# xbee_compat.net
KiCad netlist of a schematic drawn in EAGLE
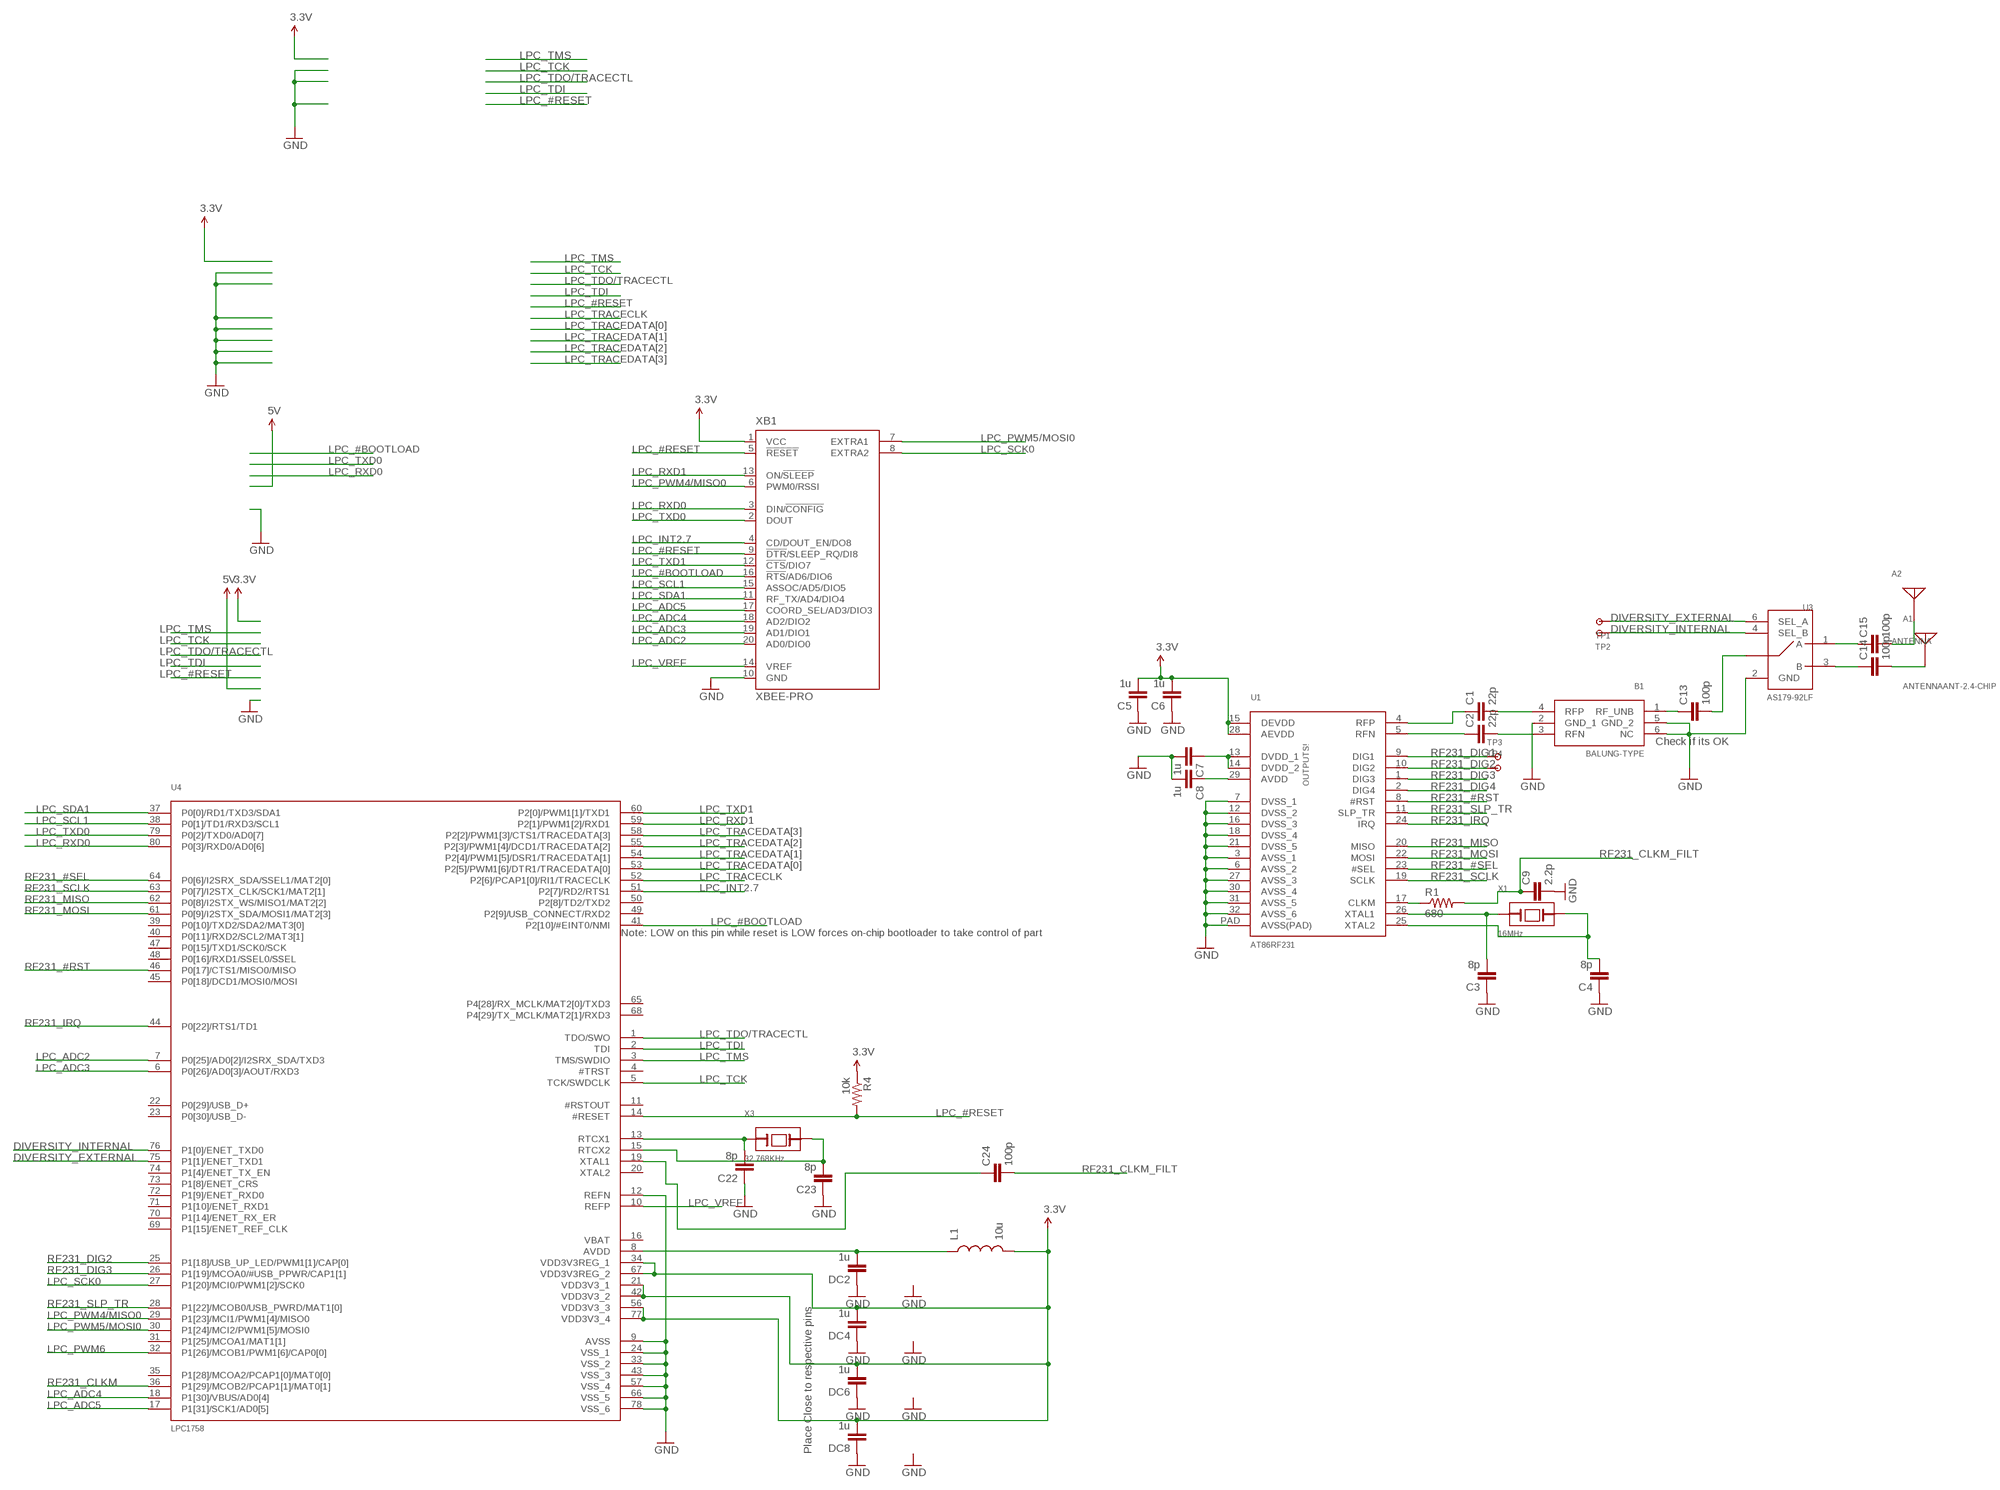
[diagram p0: schematic, sheet 1]

(export (version "E")
  (design (tool "Eeschema 10.0.6"))
  (components
    (comp (ref "A1")
      (value "ANTENNAANT-2.4-CHIP")
      (footprint "eagle-import:ANT-2.4-CHP")
      (libsource (lib "eagle-import") (part "ANTENNAANT-2.4-CHIP"))
    )
    (comp (ref "A2")
      (value "ANTENNA")
      (footprint "eagle-import:CONREVSMA003.031")
      (libsource (lib "eagle-import") (part "ANTENNA"))
    )
    (comp (ref "B1")
      (value "BALUNG-TYPE")
      (footprint "eagle-import:MURATA_LDB_BALUN")
      (libsource (lib "eagle-import") (part "BALUNG-TYPE"))
    )
    (comp (ref "C1")
      (value "22p")
      (footprint "eagle-import:C0402")
      (libsource (lib "eagle-import") (part "CAP0402"))
    )
    (comp (ref "C2")
      (value "22p")
      (footprint "eagle-import:C0402")
      (libsource (lib "eagle-import") (part "CAP0402"))
    )
    (comp (ref "C3")
      (value "8p")
      (footprint "eagle-import:C0402")
      (libsource (lib "eagle-import") (part "CAP0402"))
    )
    (comp (ref "C4")
      (value "8p")
      (footprint "eagle-import:C0402")
      (libsource (lib "eagle-import") (part "CAP0402"))
    )
    (comp (ref "C5")
      (value "1u")
      (footprint "eagle-import:C0402")
      (libsource (lib "eagle-import") (part "CAP0402"))
    )
    (comp (ref "C6")
      (value "1u")
      (footprint "eagle-import:C0402")
      (libsource (lib "eagle-import") (part "CAP0402"))
    )
    (comp (ref "C7")
      (value "1u")
      (footprint "eagle-import:C0402")
      (libsource (lib "eagle-import") (part "CAP0402"))
    )
    (comp (ref "C8")
      (value "1u")
      (footprint "eagle-import:C0402")
      (libsource (lib "eagle-import") (part "CAP0402"))
    )
    (comp (ref "C9")
      (value "2.2p")
      (footprint "eagle-import:C0402")
      (libsource (lib "eagle-import") (part "CAP0402"))
    )
    (comp (ref "C13")
      (value "100p")
      (footprint "eagle-import:C0402")
      (libsource (lib "eagle-import") (part "CAP0402"))
    )
    (comp (ref "C14")
      (value "100p")
      (footprint "eagle-import:C0402")
      (libsource (lib "eagle-import") (part "CAP0402"))
    )
    (comp (ref "C15")
      (value "100p")
      (footprint "eagle-import:C0402")
      (libsource (lib "eagle-import") (part "CAP0402"))
    )
    (comp (ref "C22")
      (value "8p")
      (footprint "eagle-import:C0402")
      (libsource (lib "eagle-import") (part "CAP0402"))
    )
    (comp (ref "C23")
      (value "8p")
      (footprint "eagle-import:C0402")
      (libsource (lib "eagle-import") (part "CAP0402"))
    )
    (comp (ref "C24")
      (value "100p")
      (footprint "eagle-import:C0402")
      (libsource (lib "eagle-import") (part "CAP0402"))
    )
    (comp (ref "DC2")
      (value "1u")
      (footprint "eagle-import:C0402")
      (libsource (lib "eagle-import") (part "CAP0402"))
    )
    (comp (ref "DC4")
      (value "1u")
      (footprint "eagle-import:C0402")
      (libsource (lib "eagle-import") (part "CAP0402"))
    )
    (comp (ref "DC6")
      (value "1u")
      (footprint "eagle-import:C0402")
      (libsource (lib "eagle-import") (part "CAP0402"))
    )
    (comp (ref "DC8")
      (value "1u")
      (footprint "eagle-import:C0402")
      (libsource (lib "eagle-import") (part "CAP0402"))
    )
    (comp (ref "L1")
      (value "10u")
      (footprint "eagle-import:0603")
      (libsource (lib "eagle-import") (part "INDUCTOR0603"))
    )
    (comp (ref "R1")
      (value "680")
      (footprint "eagle-import:C0402")
      (libsource (lib "eagle-import") (part "RESISTOR0402"))
    )
    (comp (ref "R4")
      (value "10k")
      (footprint "eagle-import:C0402")
      (libsource (lib "eagle-import") (part "RESISTOR0402"))
    )
    (comp (ref "TP1")
      (value "TESTPOINTSMALLEST")
      (footprint "eagle-import:TESTPOINT")
      (libsource (lib "eagle-import") (part "TESTPOINTSMALLEST"))
    )
    (comp (ref "TP2")
      (value "TESTPOINTSMALLEST")
      (footprint "eagle-import:TESTPOINT")
      (libsource (lib "eagle-import") (part "TESTPOINTSMALLEST"))
    )
    (comp (ref "TP3")
      (value "TESTPOINTSMALLEST")
      (footprint "eagle-import:TESTPOINT")
      (libsource (lib "eagle-import") (part "TESTPOINTSMALLEST"))
    )
    (comp (ref "TP4")
      (value "TESTPOINTSMALLEST")
      (footprint "eagle-import:TESTPOINT")
      (libsource (lib "eagle-import") (part "TESTPOINTSMALLEST"))
    )
    (comp (ref "U1")
      (value "AT86RF231")
      (footprint "eagle-import:ATRF231_32QN2")
      (libsource (lib "eagle-import") (part "AT86RF231"))
    )
    (comp (ref "U3")
      (value "AS179-92LF")
      (footprint "eagle-import:SC-70")
      (libsource (lib "eagle-import") (part "AS179-92LF"))
    )
    (comp (ref "U4")
      (value "LPC1758")
      (footprint "eagle-import:LPC1758_LQFP80")
      (libsource (lib "eagle-import") (part "LPC1758"))
    )
    (comp (ref "X1")
      (value "16MHz")
      (footprint "eagle-import:CX3225SA")
      (libsource (lib "eagle-import") (part "XTALCX3225SA"))
    )
    (comp (ref "X3")
      (value "32.768KHz")
      (footprint "eagle-import:ABS07")
      (libsource (lib "eagle-import") (part "XTALABS07"))
    )
    (comp (ref "XB1")
      (value "XBEE-PRO")
      (footprint "eagle-import:XBEE-PRO")
      (libsource (lib "eagle-import") (part "XBEE-PRO"))
    )
  )
  (nets
    (net (code "1") (name "/DIVERSITY_EXTERNAL") (class "Default")
      (node (ref "TP1") (pin "P$1") (pinfunction "P$1_P$1") (pintype "bidirectional"))
      (node (ref "U3") (pin "6") (pinfunction "SEL_A_6") (pintype "bidirectional"))
      (node (ref "U4") (pin "75") (pinfunction "P1[1]/ENET_TXD1_75") (pintype "bidirectional"))
    )
    (net (code "2") (name "/DIVERSITY_INTERNAL") (class "Default")
      (node (ref "TP2") (pin "P$1") (pinfunction "P$1_P$1") (pintype "bidirectional"))
      (node (ref "U3") (pin "4") (pinfunction "SEL_B_4") (pintype "bidirectional"))
      (node (ref "U4") (pin "76") (pinfunction "P1[0]/ENET_TXD0_76") (pintype "bidirectional"))
    )
    (net (code "3") (name "/LPC_#BOOTLOAD") (class "Default")
      (node (ref "U4") (pin "41") (pinfunction "P2[10]/#EINT0/NMI_41") (pintype "bidirectional"))
      (node (ref "XB1") (pin "16") (pinfunction "~{RTS}/AD6/DIO6_16") (pintype "bidirectional"))
    )
    (net (code "4") (name "/LPC_#RESET") (class "Default")
      (node (ref "R4") (pin "2") (pinfunction "2_2") (pintype "passive"))
      (node (ref "U4") (pin "14") (pinfunction "#RESET_14") (pintype "bidirectional"))
      (node (ref "XB1") (pin "5") (pinfunction "~{RESET}_5") (pintype "input"))
      (node (ref "XB1") (pin "9") (pinfunction "~{DTR}/SLEEP_RQ/DI8_9") (pintype "bidirectional"))
    )
    (net (code "5") (name "/LPC_ADC2") (class "Default")
      (node (ref "U4") (pin "7") (pinfunction "P0[25]/AD0[2]/I2SRX_SDA/TXD3_7") (pintype "bidirectional"))
      (node (ref "XB1") (pin "20") (pinfunction "AD0/DIO0_20") (pintype "bidirectional"))
    )
    (net (code "6") (name "/LPC_ADC3") (class "Default")
      (node (ref "U4") (pin "6") (pinfunction "P0[26]/AD0[3]/AOUT/RXD3_6") (pintype "bidirectional"))
      (node (ref "XB1") (pin "19") (pinfunction "AD1/DIO1_19") (pintype "bidirectional"))
    )
    (net (code "7") (name "/LPC_ADC4") (class "Default")
      (node (ref "U4") (pin "18") (pinfunction "P1[30]/VBUS/AD0[4]_18") (pintype "bidirectional"))
      (node (ref "XB1") (pin "18") (pinfunction "AD2/DIO2_18") (pintype "bidirectional"))
    )
    (net (code "8") (name "/LPC_ADC5") (class "Default")
      (node (ref "U4") (pin "17") (pinfunction "P1[31]/SCK1/AD0[5]_17") (pintype "bidirectional"))
      (node (ref "XB1") (pin "17") (pinfunction "COORD_SEL/AD3/DIO3_17") (pintype "bidirectional"))
    )
    (net (code "9") (name "/LPC_INT2.7") (class "Default")
      (node (ref "U4") (pin "51") (pinfunction "P2[7]/RD2/RTS1_51") (pintype "bidirectional"))
      (node (ref "XB1") (pin "4") (pinfunction "CD/DOUT_EN/DO8_4") (pintype "output"))
    )
    (net (code "10") (name "/LPC_PWM4{slash}MISO0") (class "Default")
      (node (ref "U4") (pin "29") (pinfunction "P1[23]/MCI1/PWM1[4]/MISO0_29") (pintype "bidirectional"))
      (node (ref "XB1") (pin "6") (pinfunction "PWM0/RSSI_6") (pintype "output"))
    )
    (net (code "11") (name "/LPC_PWM5{slash}MOSI0") (class "Default")
      (node (ref "U4") (pin "30") (pinfunction "P1[24]/MCI2/PWM1[5]/MOSI0_30") (pintype "bidirectional"))
      (node (ref "XB1") (pin "7") (pinfunction "EXTRA1_7") (pintype "bidirectional"))
    )
    (net (code "12") (name "/LPC_PWM6") (class "Default")
      (node (ref "U4") (pin "32") (pinfunction "P1[26]/MCOB1/PWM1[6]/CAP0[0]_32") (pintype "bidirectional"))
    )
    (net (code "13") (name "/LPC_RXD0") (class "Default")
      (node (ref "U4") (pin "80") (pinfunction "P0[3]/RXD0/AD0[6]_80") (pintype "bidirectional"))
      (node (ref "XB1") (pin "3") (pinfunction "DIN/~{CONFIG}_3") (pintype "input"))
    )
    (net (code "14") (name "/LPC_RXD1") (class "Default")
      (node (ref "U4") (pin "59") (pinfunction "P2[1]/PWM1[2]/RXD1_59") (pintype "bidirectional"))
      (node (ref "XB1") (pin "13") (pinfunction "ON/~{SLEEP}_13") (pintype "output"))
    )
    (net (code "15") (name "/LPC_SCK0") (class "Default")
      (node (ref "U4") (pin "27") (pinfunction "P1[20]/MCI0/PWM1[2]/SCK0_27") (pintype "bidirectional"))
      (node (ref "XB1") (pin "8") (pinfunction "EXTRA2_8") (pintype "bidirectional"))
    )
    (net (code "16") (name "/LPC_SCL1") (class "Default")
      (node (ref "U4") (pin "38") (pinfunction "P0[1]/TD1/RXD3/SCL1_38") (pintype "bidirectional"))
      (node (ref "XB1") (pin "15") (pinfunction "ASSOC/AD5/DIO5_15") (pintype "bidirectional"))
    )
    (net (code "17") (name "/LPC_SDA1") (class "Default")
      (node (ref "U4") (pin "37") (pinfunction "P0[0]/RD1/TXD3/SDA1_37") (pintype "bidirectional"))
      (node (ref "XB1") (pin "11") (pinfunction "RF_TX/AD4/DIO4_11") (pintype "bidirectional"))
    )
    (net (code "18") (name "/LPC_TCK") (class "Default")
      (node (ref "U4") (pin "5") (pinfunction "TCK/SWDCLK_5") (pintype "bidirectional"))
    )
    (net (code "19") (name "/LPC_TDI") (class "Default")
      (node (ref "U4") (pin "2") (pinfunction "TDI_2") (pintype "bidirectional"))
    )
    (net (code "20") (name "/LPC_TDO{slash}TRACECTL") (class "Default")
      (node (ref "U4") (pin "1") (pinfunction "TDO/SWO_1") (pintype "bidirectional"))
    )
    (net (code "21") (name "/LPC_TMS") (class "Default")
      (node (ref "U4") (pin "3") (pinfunction "TMS/SWDIO_3") (pintype "bidirectional"))
    )
    (net (code "22") (name "/LPC_TRACECLK") (class "Default")
      (node (ref "U4") (pin "52") (pinfunction "P2[6]/PCAP1[0]/RI1/TRACECLK_52") (pintype "bidirectional"))
    )
    (net (code "23") (name "/LPC_TRACEDATA[0]") (class "Default")
      (node (ref "U4") (pin "53") (pinfunction "P2[5]/PWM1[6]/DTR1/TRACEDATA[0]_53") (pintype "bidirectional"))
    )
    (net (code "24") (name "/LPC_TRACEDATA[1]") (class "Default")
      (node (ref "U4") (pin "54") (pinfunction "P2[4]/PWM1[5]/DSR1/TRACEDATA[1]_54") (pintype "bidirectional"))
    )
    (net (code "25") (name "/LPC_TRACEDATA[2]") (class "Default")
      (node (ref "U4") (pin "55") (pinfunction "P2[3]/PWM1[4]/DCD1/TRACEDATA[2]_55") (pintype "bidirectional"))
    )
    (net (code "26") (name "/LPC_TRACEDATA[3]") (class "Default")
      (node (ref "U4") (pin "58") (pinfunction "P2[2]/PWM1[3]/CTS1/TRACEDATA[3]_58") (pintype "bidirectional"))
    )
    (net (code "27") (name "/LPC_TXD0") (class "Default")
      (node (ref "U4") (pin "79") (pinfunction "P0[2]/TXD0/AD0[7]_79") (pintype "bidirectional"))
      (node (ref "XB1") (pin "2") (pinfunction "DOUT_2") (pintype "output"))
    )
    (net (code "28") (name "/LPC_TXD1") (class "Default")
      (node (ref "U4") (pin "60") (pinfunction "P2[0]/PWM1[1]/TXD1_60") (pintype "bidirectional"))
      (node (ref "XB1") (pin "12") (pinfunction "~{CTS}/DIO7_12") (pintype "bidirectional"))
    )
    (net (code "29") (name "/LPC_VREF") (class "Default")
      (node (ref "U4") (pin "10") (pinfunction "REFP_10") (pintype "bidirectional"))
      (node (ref "XB1") (pin "14") (pinfunction "VREF_14") (pintype "input"))
    )
    (net (code "30") (name "/RF231_#RST") (class "Default")
      (node (ref "U1") (pin "8") (pinfunction "#RST_8") (pintype "bidirectional"))
      (node (ref "U4") (pin "46") (pinfunction "P0[17]/CTS1/MISO0/MISO_46") (pintype "bidirectional"))
    )
    (net (code "31") (name "/RF231_#SEL") (class "Default")
      (node (ref "U1") (pin "23") (pinfunction "#SEL_23") (pintype "bidirectional"))
      (node (ref "U4") (pin "64") (pinfunction "P0[6]/I2SRX_SDA/SSEL1/MAT2[0]_64") (pintype "bidirectional"))
    )
    (net (code "32") (name "/RF231_CLKM") (class "Default")
      (node (ref "U4") (pin "36") (pinfunction "P1[29]/MCOB2/PCAP1[1]/MAT0[1]_36") (pintype "bidirectional"))
    )
    (net (code "33") (name "/RF231_CLKM_FILT") (class "Default")
      (node (ref "C24") (pin "2") (pinfunction "2_2") (pintype "passive"))
      (node (ref "C9") (pin "1") (pinfunction "1_1") (pintype "passive"))
      (node (ref "R1") (pin "2") (pinfunction "2_2") (pintype "passive"))
    )
    (net (code "34") (name "/RF231_DIG1") (class "Default")
      (node (ref "TP3") (pin "P$1") (pinfunction "P$1_P$1") (pintype "bidirectional"))
      (node (ref "U1") (pin "9") (pinfunction "DIG1_9") (pintype "bidirectional"))
    )
    (net (code "35") (name "/RF231_DIG2") (class "Default")
      (node (ref "TP4") (pin "P$1") (pinfunction "P$1_P$1") (pintype "bidirectional"))
      (node (ref "U1") (pin "10") (pinfunction "DIG2_10") (pintype "bidirectional"))
      (node (ref "U4") (pin "25") (pinfunction "P1[18]/USB_UP_LED/PWM1[1]/CAP[0]_25") (pintype "bidirectional"))
    )
    (net (code "36") (name "/RF231_DIG3") (class "Default")
      (node (ref "U1") (pin "1") (pinfunction "DIG3_1") (pintype "bidirectional"))
      (node (ref "U4") (pin "26") (pinfunction "P1[19]/MCOA0/#USB_PPWR/CAP1[1]_26") (pintype "bidirectional"))
    )
    (net (code "37") (name "/RF231_DIG4") (class "Default")
      (node (ref "U1") (pin "2") (pinfunction "DIG4_2") (pintype "bidirectional"))
    )
    (net (code "38") (name "/RF231_IRQ") (class "Default")
      (node (ref "U1") (pin "24") (pinfunction "IRQ_24") (pintype "bidirectional"))
      (node (ref "U4") (pin "44") (pinfunction "P0[22]/RTS1/TD1_44") (pintype "bidirectional"))
    )
    (net (code "39") (name "/RF231_MISO") (class "Default")
      (node (ref "U1") (pin "20") (pinfunction "MISO_20") (pintype "bidirectional"))
      (node (ref "U4") (pin "62") (pinfunction "P0[8]/I2STX_WS/MISO1/MAT2[2]_62") (pintype "bidirectional"))
    )
    (net (code "40") (name "/RF231_MOSI") (class "Default")
      (node (ref "U1") (pin "22") (pinfunction "MOSI_22") (pintype "bidirectional"))
      (node (ref "U4") (pin "61") (pinfunction "P0[9]/I2STX_SDA/MOSI1/MAT2[3]_61") (pintype "bidirectional"))
    )
    (net (code "41") (name "/RF231_SCLK") (class "Default")
      (node (ref "U1") (pin "19") (pinfunction "SCLK_19") (pintype "bidirectional"))
      (node (ref "U4") (pin "63") (pinfunction "P0[7]/I2STX_CLK/SCK1/MAT2[1]_63") (pintype "bidirectional"))
    )
    (net (code "42") (name "/RF231_SLP_TR") (class "Default")
      (node (ref "U1") (pin "11") (pinfunction "SLP_TR_11") (pintype "bidirectional"))
      (node (ref "U4") (pin "28") (pinfunction "P1[22]/MCOB0/USB_PWRD/MAT1[0]_28") (pintype "bidirectional"))
    )
    (net (code "43") (name "3.3V") (class "Default")
      (node (ref "C5") (pin "2") (pinfunction "2_2") (pintype "passive"))
      (node (ref "C6") (pin "2") (pinfunction "2_2") (pintype "passive"))
      (node (ref "DC4") (pin "2") (pinfunction "2_2") (pintype "passive"))
      (node (ref "DC6") (pin "2") (pinfunction "2_2") (pintype "passive"))
      (node (ref "DC8") (pin "2") (pinfunction "2_2") (pintype "passive"))
      (node (ref "L1") (pin "2") (pinfunction "2_2") (pintype "passive"))
      (node (ref "R4") (pin "1") (pinfunction "1_1") (pintype "passive"))
      (node (ref "U1") (pin "15") (pinfunction "DEVDD_15") (pintype "bidirectional"))
      (node (ref "U1") (pin "28") (pinfunction "AEVDD_28") (pintype "bidirectional"))
      (node (ref "U4") (pin "21") (pinfunction "VDD3V3_1_21") (pintype "bidirectional"))
      (node (ref "U4") (pin "34") (pinfunction "VDD3V3REG_1_34") (pintype "bidirectional"))
      (node (ref "U4") (pin "42") (pinfunction "VDD3V3_2_42") (pintype "bidirectional"))
      (node (ref "U4") (pin "56") (pinfunction "VDD3V3_3_56") (pintype "bidirectional"))
      (node (ref "U4") (pin "67") (pinfunction "VDD3V3REG_2_67") (pintype "bidirectional"))
      (node (ref "U4") (pin "77") (pinfunction "VDD3V3_4_77") (pintype "bidirectional"))
      (node (ref "XB1") (pin "1") (pinfunction "VCC_1") (pintype "power_in"))
    )
    (net (code "45") (name "GND") (class "Default")
      (node (ref "B1") (pin "2") (pinfunction "GND_1_2") (pintype "bidirectional"))
      (node (ref "B1") (pin "5") (pinfunction "GND_2_5") (pintype "bidirectional"))
      (node (ref "B1") (pin "6") (pinfunction "NC_6") (pintype "bidirectional"))
      (node (ref "C22") (pin "1") (pinfunction "1_1") (pintype "passive"))
      (node (ref "C23") (pin "1") (pinfunction "1_1") (pintype "passive"))
      (node (ref "C3") (pin "1") (pinfunction "1_1") (pintype "passive"))
      (node (ref "C4") (pin "1") (pinfunction "1_1") (pintype "passive"))
      (node (ref "C5") (pin "1") (pinfunction "1_1") (pintype "passive"))
      (node (ref "C6") (pin "1") (pinfunction "1_1") (pintype "passive"))
      (node (ref "C7") (pin "2") (pinfunction "2_2") (pintype "passive"))
      (node (ref "C8") (pin "2") (pinfunction "2_2") (pintype "passive"))
      (node (ref "C9") (pin "2") (pinfunction "2_2") (pintype "passive"))
      (node (ref "DC2") (pin "1") (pinfunction "1_1") (pintype "passive"))
      (node (ref "DC4") (pin "1") (pinfunction "1_1") (pintype "passive"))
      (node (ref "DC6") (pin "1") (pinfunction "1_1") (pintype "passive"))
      (node (ref "DC8") (pin "1") (pinfunction "1_1") (pintype "passive"))
      (node (ref "U1") (pin "12") (pinfunction "DVSS_2_12") (pintype "bidirectional"))
      (node (ref "U1") (pin "16") (pinfunction "DVSS_3_16") (pintype "bidirectional"))
      (node (ref "U1") (pin "18") (pinfunction "DVSS_4_18") (pintype "bidirectional"))
      (node (ref "U1") (pin "21") (pinfunction "DVSS_5_21") (pintype "bidirectional"))
      (node (ref "U1") (pin "27") (pinfunction "AVSS_3_27") (pintype "bidirectional"))
      (node (ref "U1") (pin "3") (pinfunction "AVSS_1_3") (pintype "bidirectional"))
      (node (ref "U1") (pin "30") (pinfunction "AVSS_4_30") (pintype "bidirectional"))
      (node (ref "U1") (pin "31") (pinfunction "AVSS_5_31") (pintype "bidirectional"))
      (node (ref "U1") (pin "32") (pinfunction "AVSS_6_32") (pintype "bidirectional"))
      (node (ref "U1") (pin "6") (pinfunction "AVSS_2_6") (pintype "bidirectional"))
      (node (ref "U1") (pin "7") (pinfunction "DVSS_1_7") (pintype "bidirectional"))
      (node (ref "U1") (pin "PAD") (pinfunction "AVSS(PAD)_PAD") (pintype "bidirectional"))
      (node (ref "U3") (pin "2") (pinfunction "GND_2") (pintype "bidirectional"))
      (node (ref "U4") (pin "12") (pinfunction "REFN_12") (pintype "bidirectional"))
      (node (ref "U4") (pin "24") (pinfunction "VSS_1_24") (pintype "bidirectional"))
      (node (ref "U4") (pin "33") (pinfunction "VSS_2_33") (pintype "bidirectional"))
      (node (ref "U4") (pin "43") (pinfunction "VSS_3_43") (pintype "bidirectional"))
      (node (ref "U4") (pin "57") (pinfunction "VSS_4_57") (pintype "bidirectional"))
      (node (ref "U4") (pin "66") (pinfunction "VSS_5_66") (pintype "bidirectional"))
      (node (ref "U4") (pin "78") (pinfunction "VSS_6_78") (pintype "bidirectional"))
      (node (ref "U4") (pin "9") (pinfunction "AVSS_9") (pintype "bidirectional"))
      (node (ref "XB1") (pin "10") (pinfunction "GND_10") (pintype "power_in"))
    )
    (net (code "46") (name "Net-(A1-P$1)") (class "Default")
      (node (ref "A1") (pin "CON") (pinfunction "P$1_CON") (pintype "bidirectional"))
      (node (ref "C14") (pin "2") (pinfunction "2_2") (pintype "passive"))
    )
    (net (code "47") (name "Net-(A2-P$1)") (class "Default")
      (node (ref "A2") (pin "CON") (pinfunction "P$1_CON") (pintype "bidirectional"))
      (node (ref "C15") (pin "2") (pinfunction "2_2") (pintype "passive"))
    )
    (net (code "48") (name "Net-(B1-RFN)") (class "Default")
      (node (ref "B1") (pin "3") (pinfunction "RFN_3") (pintype "bidirectional"))
      (node (ref "C2") (pin "2") (pinfunction "2_2") (pintype "passive"))
    )
    (net (code "49") (name "Net-(B1-RFP)") (class "Default")
      (node (ref "B1") (pin "4") (pinfunction "RFP_4") (pintype "bidirectional"))
      (node (ref "C1") (pin "2") (pinfunction "2_2") (pintype "passive"))
    )
    (net (code "50") (name "Net-(B1-RF_UNB)") (class "Default")
      (node (ref "B1") (pin "1") (pinfunction "RF_UNB_1") (pintype "bidirectional"))
      (node (ref "C13") (pin "1") (pinfunction "1_1") (pintype "passive"))
    )
    (net (code "51") (name "Net-(U1-AVDD)") (class "Default")
      (node (ref "C8") (pin "1") (pinfunction "1_1") (pintype "passive"))
      (node (ref "U1") (pin "29") (pinfunction "AVDD_29") (pintype "bidirectional"))
    )
    (net (code "52") (name "Net-(U1-CLKM)") (class "Default")
      (node (ref "R1") (pin "1") (pinfunction "1_1") (pintype "passive"))
      (node (ref "U1") (pin "17") (pinfunction "CLKM_17") (pintype "bidirectional"))
    )
    (net (code "53") (name "Net-(U1-DVDD_1)") (class "Default")
      (node (ref "C7") (pin "1") (pinfunction "1_1") (pintype "passive"))
      (node (ref "U1") (pin "13") (pinfunction "DVDD_1_13") (pintype "bidirectional"))
      (node (ref "U1") (pin "14") (pinfunction "DVDD_2_14") (pintype "bidirectional"))
    )
    (net (code "54") (name "Net-(U1-RFN)") (class "Default")
      (node (ref "C2") (pin "1") (pinfunction "1_1") (pintype "passive"))
      (node (ref "U1") (pin "5") (pinfunction "RFN_5") (pintype "bidirectional"))
    )
    (net (code "55") (name "Net-(U1-RFP)") (class "Default")
      (node (ref "C1") (pin "1") (pinfunction "1_1") (pintype "passive"))
      (node (ref "U1") (pin "4") (pinfunction "RFP_4") (pintype "bidirectional"))
    )
    (net (code "56") (name "Net-(U1-XTAL1)") (class "Default")
      (node (ref "C3") (pin "2") (pinfunction "2_2") (pintype "passive"))
      (node (ref "U1") (pin "26") (pinfunction "XTAL1_26") (pintype "bidirectional"))
      (node (ref "X1") (pin "3") (pinfunction "A_3") (pintype "bidirectional"))
    )
    (net (code "57") (name "Net-(U1-XTAL2)") (class "Default")
      (node (ref "C4") (pin "2") (pinfunction "2_2") (pintype "passive"))
      (node (ref "U1") (pin "25") (pinfunction "XTAL2_25") (pintype "bidirectional"))
      (node (ref "X1") (pin "1") (pinfunction "B_1") (pintype "bidirectional"))
    )
    (net (code "58") (name "Net-(U3-A)") (class "Default")
      (node (ref "C15") (pin "1") (pinfunction "1_1") (pintype "passive"))
      (node (ref "U3") (pin "1") (pinfunction "A_1") (pintype "bidirectional"))
    )
    (net (code "59") (name "Net-(U3-B)") (class "Default")
      (node (ref "C14") (pin "1") (pinfunction "1_1") (pintype "passive"))
      (node (ref "U3") (pin "3") (pinfunction "B_3") (pintype "bidirectional"))
    )
    (net (code "60") (name "Net-(U3-W)") (class "Default")
      (node (ref "C13") (pin "2") (pinfunction "2_2") (pintype "passive"))
      (node (ref "U3") (pin "5") (pinfunction "W_5") (pintype "bidirectional"))
    )
    (net (code "61") (name "Net-(U4-AVDD)") (class "Default")
      (node (ref "DC2") (pin "2") (pinfunction "2_2") (pintype "passive"))
      (node (ref "L1") (pin "1") (pinfunction "1_1") (pintype "passive"))
      (node (ref "U4") (pin "8") (pinfunction "AVDD_8") (pintype "bidirectional"))
    )
    (net (code "62") (name "Net-(U4-RTCX1)") (class "Default")
      (node (ref "C22") (pin "2") (pinfunction "2_2") (pintype "passive"))
      (node (ref "U4") (pin "13") (pinfunction "RTCX1_13") (pintype "bidirectional"))
      (node (ref "X3") (pin "1") (pinfunction "A_1") (pintype "bidirectional"))
    )
    (net (code "63") (name "Net-(U4-RTCX2)") (class "Default")
      (node (ref "C23") (pin "2") (pinfunction "2_2") (pintype "passive"))
      (node (ref "U4") (pin "15") (pinfunction "RTCX2_15") (pintype "bidirectional"))
      (node (ref "X3") (pin "2") (pinfunction "B_2") (pintype "bidirectional"))
    )
    (net (code "64") (name "Net-(U4-XTAL1)") (class "Default")
      (node (ref "C24") (pin "1") (pinfunction "1_1") (pintype "passive"))
      (node (ref "U4") (pin "19") (pinfunction "XTAL1_19") (pintype "bidirectional"))
    )
    (net (code "65") (name "unconnected-(U4-#RSTOUT-Pad11)") (class "Default")
      (node (ref "U4") (pin "11") (pinfunction "#RSTOUT_11") (pintype "bidirectional"))
    )
    (net (code "66") (name "unconnected-(U4-#TRST-Pad4)") (class "Default")
      (node (ref "U4") (pin "4") (pinfunction "#TRST_4") (pintype "bidirectional"))
    )
    (net (code "67") (name "unconnected-(U4-P0[10]{slash}TXD2{slash}SDA2{slash}MAT3[0]-Pad39)") (class "Default")
      (node (ref "U4") (pin "39") (pinfunction "P0[10]/TXD2/SDA2/MAT3[0]_39") (pintype "bidirectional"))
    )
    (net (code "68") (name "unconnected-(U4-P0[11]{slash}RXD2{slash}SCL2{slash}MAT3[1]-Pad40)") (class "Default")
      (node (ref "U4") (pin "40") (pinfunction "P0[11]/RXD2/SCL2/MAT3[1]_40") (pintype "bidirectional"))
    )
    (net (code "69") (name "unconnected-(U4-P0[15]{slash}TXD1{slash}SCK0{slash}SCK-Pad47)") (class "Default")
      (node (ref "U4") (pin "47") (pinfunction "P0[15]/TXD1/SCK0/SCK_47") (pintype "bidirectional"))
    )
    (net (code "70") (name "unconnected-(U4-P0[16]{slash}RXD1{slash}SSEL0{slash}SSEL-Pad48)") (class "Default")
      (node (ref "U4") (pin "48") (pinfunction "P0[16]/RXD1/SSEL0/SSEL_48") (pintype "bidirectional"))
    )
    (net (code "71") (name "unconnected-(U4-P0[18]{slash}DCD1{slash}MOSI0{slash}MOSI-Pad45)") (class "Default")
      (node (ref "U4") (pin "45") (pinfunction "P0[18]/DCD1/MOSI0/MOSI_45") (pintype "bidirectional"))
    )
    (net (code "72") (name "unconnected-(U4-P0[29]{slash}USB_D+-Pad22)") (class "Default")
      (node (ref "U4") (pin "22") (pinfunction "P0[29]/USB_D+_22") (pintype "bidirectional"))
    )
    (net (code "73") (name "unconnected-(U4-P0[30]{slash}USB_D--Pad23)") (class "Default")
      (node (ref "U4") (pin "23") (pinfunction "P0[30]/USB_D-_23") (pintype "bidirectional"))
    )
    (net (code "74") (name "unconnected-(U4-P1[4]{slash}ENET_TX_EN-Pad74)") (class "Default")
      (node (ref "U4") (pin "74") (pinfunction "P1[4]/ENET_TX_EN_74") (pintype "bidirectional"))
    )
    (net (code "75") (name "unconnected-(U4-P1[8]{slash}ENET_CRS-Pad73)") (class "Default")
      (node (ref "U4") (pin "73") (pinfunction "P1[8]/ENET_CRS_73") (pintype "bidirectional"))
    )
    (net (code "76") (name "unconnected-(U4-P1[9]{slash}ENET_RXD0-Pad72)") (class "Default")
      (node (ref "U4") (pin "72") (pinfunction "P1[9]/ENET_RXD0_72") (pintype "bidirectional"))
    )
    (net (code "77") (name "unconnected-(U4-P1[10]{slash}ENET_RXD1-Pad71)") (class "Default")
      (node (ref "U4") (pin "71") (pinfunction "P1[10]/ENET_RXD1_71") (pintype "bidirectional"))
    )
    (net (code "78") (name "unconnected-(U4-P1[14]{slash}ENET_RX_ER-Pad70)") (class "Default")
      (node (ref "U4") (pin "70") (pinfunction "P1[14]/ENET_RX_ER_70") (pintype "bidirectional"))
    )
    (net (code "79") (name "unconnected-(U4-P1[15]{slash}ENET_REF_CLK-Pad69)") (class "Default")
      (node (ref "U4") (pin "69") (pinfunction "P1[15]/ENET_REF_CLK_69") (pintype "bidirectional"))
    )
    (net (code "80") (name "unconnected-(U4-P1[25]{slash}MCOA1{slash}MAT1[1]-Pad31)") (class "Default")
      (node (ref "U4") (pin "31") (pinfunction "P1[25]/MCOA1/MAT1[1]_31") (pintype "bidirectional"))
    )
    (net (code "81") (name "unconnected-(U4-P1[28]{slash}MCOA2{slash}PCAP1[0]{slash}MAT0[0]-Pad35)") (class "Default")
      (node (ref "U4") (pin "35") (pinfunction "P1[28]/MCOA2/PCAP1[0]/MAT0[0]_35") (pintype "bidirectional"))
    )
    (net (code "82") (name "unconnected-(U4-P2[8]{slash}TD2{slash}TXD2-Pad50)") (class "Default")
      (node (ref "U4") (pin "50") (pinfunction "P2[8]/TD2/TXD2_50") (pintype "bidirectional"))
    )
    (net (code "83") (name "unconnected-(U4-P2[9]{slash}USB_CONNECT{slash}RXD2-Pad49)") (class "Default")
      (node (ref "U4") (pin "49") (pinfunction "P2[9]/USB_CONNECT/RXD2_49") (pintype "bidirectional"))
    )
    (net (code "84") (name "unconnected-(U4-P4[28]{slash}RX_MCLK{slash}MAT2[0]{slash}TXD3-Pad65)") (class "Default")
      (node (ref "U4") (pin "65") (pinfunction "P4[28]/RX_MCLK/MAT2[0]/TXD3_65") (pintype "bidirectional"))
    )
    (net (code "85") (name "unconnected-(U4-P4[29]{slash}TX_MCLK{slash}MAT2[1]{slash}RXD3-Pad68)") (class "Default")
      (node (ref "U4") (pin "68") (pinfunction "P4[29]/TX_MCLK/MAT2[1]/RXD3_68") (pintype "bidirectional"))
    )
    (net (code "86") (name "unconnected-(U4-VBAT-Pad16)") (class "Default")
      (node (ref "U4") (pin "16") (pinfunction "VBAT_16") (pintype "bidirectional"))
    )
    (net (code "87") (name "unconnected-(U4-XTAL2-Pad20)") (class "Default")
      (node (ref "U4") (pin "20") (pinfunction "XTAL2_20") (pintype "bidirectional"))
    )
  )
)
